# System_Wake_Interupt_Logic.net
KiCad netlist of a schematic drawn in Altium Designer
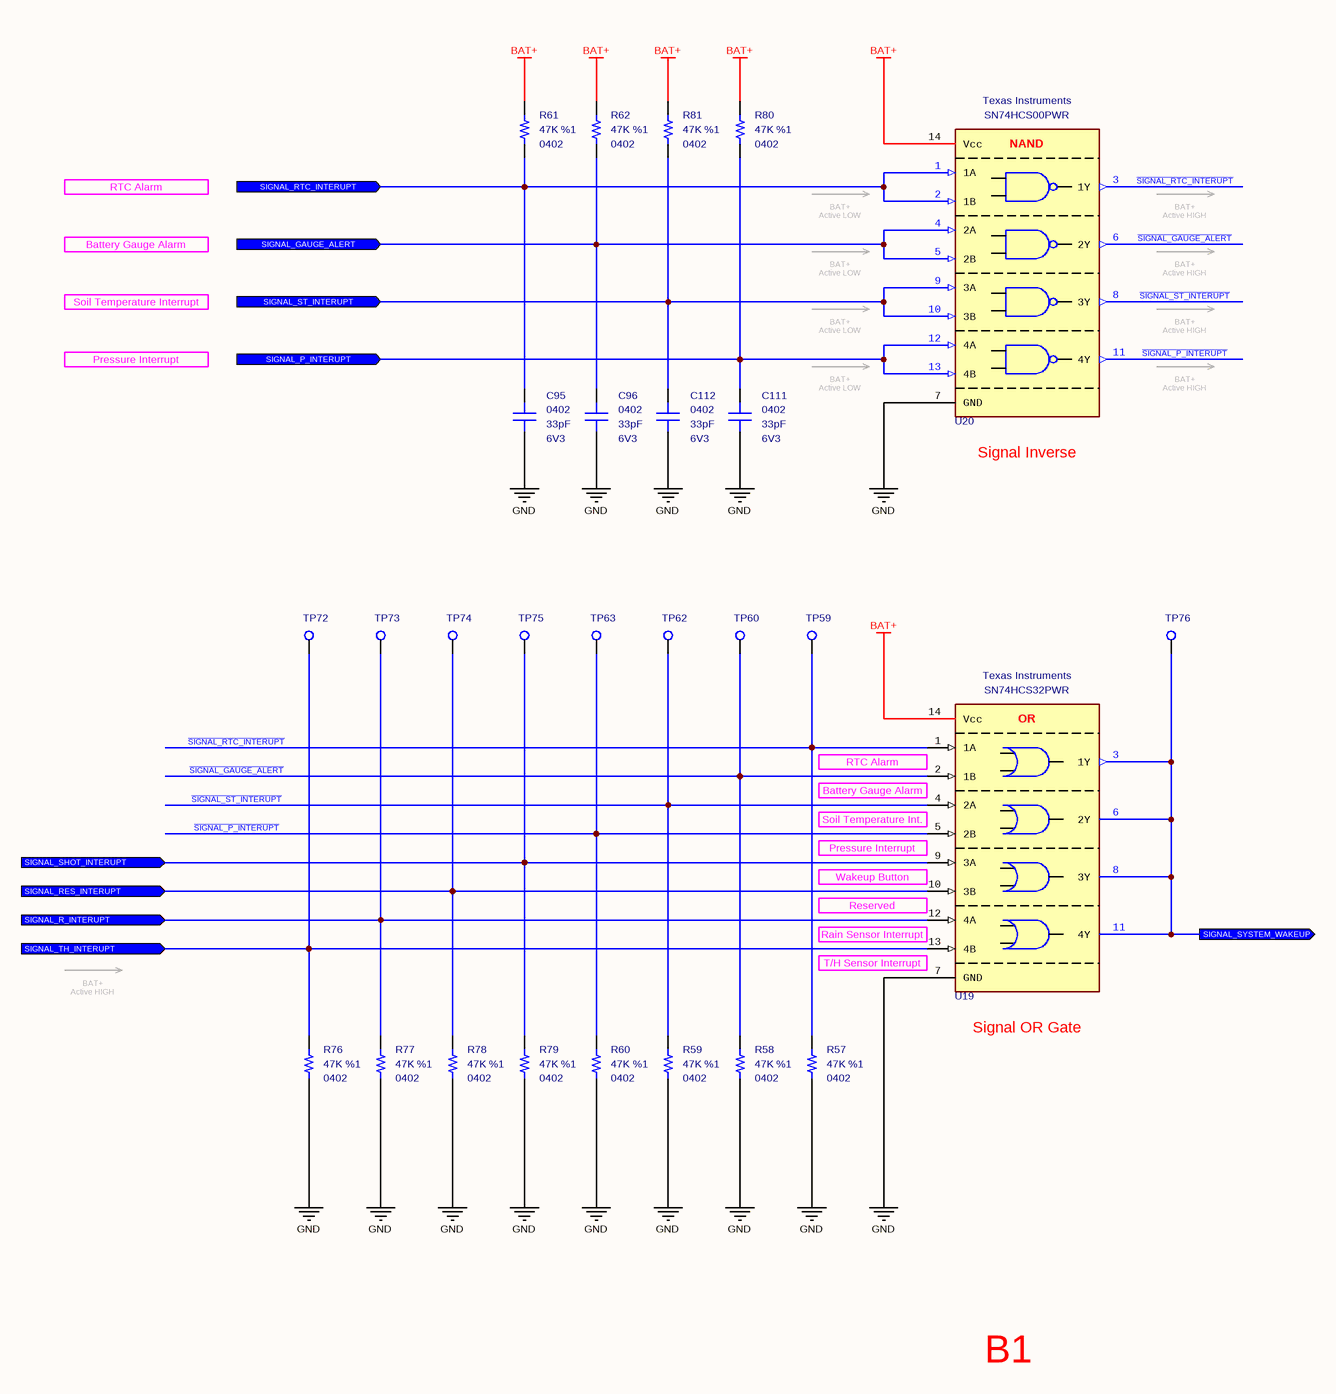
[diagram p0: System Wake Interupt Logic.SchDoc]

(export (version "E")
  (design (tool "Eeschema 10.0.6"))
  (components
    (comp (ref "C95")
      (value "33pF")
      (footprint "CAPACITOR_0402")
      (description "Capacitor - 33pF [0402] (Ceramic)")
      (fields
        (field (name "MANUFACTURER_PART_NUMBER") "C0402C330J9RACAUTO")
        (field (name "MOUSER_PART_NUMBER") "80-C0402C330J9RAUTO")
        (field (name "CASE") "0402")
        (field (name "VOLTAGE") "6V3")
      )
      (libsource (lib "Ovoo_Schematic") (part "Capacitor - 33pF [0402-6V3]"))
    )
    (comp (ref "C96")
      (value "33pF")
      (footprint "CAPACITOR_0402")
      (description "Capacitor - 33pF [0402] (Ceramic)")
      (fields
        (field (name "MANUFACTURER_PART_NUMBER") "C0402C330J9RACAUTO")
        (field (name "MOUSER_PART_NUMBER") "80-C0402C330J9RAUTO")
        (field (name "CASE") "0402")
        (field (name "VOLTAGE") "6V3")
      )
      (libsource (lib "Ovoo_Schematic") (part "Capacitor - 33pF [0402-6V3]"))
    )
    (comp (ref "C111")
      (value "33pF")
      (footprint "CAPACITOR_0402")
      (description "Capacitor - 33pF [0402] (Ceramic)")
      (fields
        (field (name "MANUFACTURER_PART_NUMBER") "C0402C330J9RACAUTO")
        (field (name "MOUSER_PART_NUMBER") "80-C0402C330J9RAUTO")
        (field (name "CASE") "0402")
        (field (name "VOLTAGE") "6V3")
      )
      (libsource (lib "Ovoo_Schematic") (part "Capacitor - 33pF [0402-6V3]"))
    )
    (comp (ref "C112")
      (value "33pF")
      (footprint "CAPACITOR_0402")
      (description "Capacitor - 33pF [0402] (Ceramic)")
      (fields
        (field (name "MANUFACTURER_PART_NUMBER") "C0402C330J9RACAUTO")
        (field (name "MOUSER_PART_NUMBER") "80-C0402C330J9RAUTO")
        (field (name "CASE") "0402")
        (field (name "VOLTAGE") "6V3")
      )
      (libsource (lib "Ovoo_Schematic") (part "Capacitor - 33pF [0402-6V3]"))
    )
    (comp (ref "R57")
      (value "47K")
      (footprint "RESISTOR_0402")
      (description "Thick Film Resistors - SMD 1/16 W 47 Kohms 1%")
      (fields
        (field (name "MANUFACTURER_PART_NUMBER") "CRCW040247K0FKED")
        (field (name "MOUSER_PART_NUMBER") "71-CRCW0402-47K-E3")
        (field (name "TOLERANCE") "%1")
        (field (name "CASE") "0402")
      )
      (libsource (lib "Ovoo_Schematic") (part "Resistor - 47K"))
    )
    (comp (ref "R58")
      (value "47K")
      (footprint "RESISTOR_0402")
      (description "Thick Film Resistors - SMD 1/16 W 47 Kohms 1%")
      (fields
        (field (name "MANUFACTURER_PART_NUMBER") "CRCW040247K0FKED")
        (field (name "MOUSER_PART_NUMBER") "71-CRCW0402-47K-E3")
        (field (name "TOLERANCE") "%1")
        (field (name "CASE") "0402")
      )
      (libsource (lib "Ovoo_Schematic") (part "Resistor - 47K"))
    )
    (comp (ref "R59")
      (value "47K")
      (footprint "RESISTOR_0402")
      (description "Thick Film Resistors - SMD 1/16 W 47 Kohms 1%")
      (fields
        (field (name "MANUFACTURER_PART_NUMBER") "CRCW040247K0FKED")
        (field (name "MOUSER_PART_NUMBER") "71-CRCW0402-47K-E3")
        (field (name "TOLERANCE") "%1")
        (field (name "CASE") "0402")
      )
      (libsource (lib "Ovoo_Schematic") (part "Resistor - 47K"))
    )
    (comp (ref "R60")
      (value "47K")
      (footprint "RESISTOR_0402")
      (description "Thick Film Resistors - SMD 1/16 W 47 Kohms 1%")
      (fields
        (field (name "MANUFACTURER_PART_NUMBER") "CRCW040247K0FKED")
        (field (name "MOUSER_PART_NUMBER") "71-CRCW0402-47K-E3")
        (field (name "TOLERANCE") "%1")
        (field (name "CASE") "0402")
      )
      (libsource (lib "Ovoo_Schematic") (part "Resistor - 47K"))
    )
    (comp (ref "R61")
      (value "47K")
      (footprint "RESISTOR_0402")
      (description "Thick Film Resistors - SMD 1/16 W 47 Kohms 1%")
      (fields
        (field (name "MANUFACTURER_PART_NUMBER") "CRCW040247K0FKED")
        (field (name "MOUSER_PART_NUMBER") "71-CRCW0402-47K-E3")
        (field (name "TOLERANCE") "%1")
        (field (name "CASE") "0402")
      )
      (libsource (lib "Ovoo_Schematic") (part "Resistor - 47K"))
    )
    (comp (ref "R62")
      (value "47K")
      (footprint "RESISTOR_0402")
      (description "Thick Film Resistors - SMD 1/16 W 47 Kohms 1%")
      (fields
        (field (name "MANUFACTURER_PART_NUMBER") "CRCW040247K0FKED")
        (field (name "MOUSER_PART_NUMBER") "71-CRCW0402-47K-E3")
        (field (name "TOLERANCE") "%1")
        (field (name "CASE") "0402")
      )
      (libsource (lib "Ovoo_Schematic") (part "Resistor - 47K"))
    )
    (comp (ref "R76")
      (value "47K")
      (footprint "RESISTOR_0402")
      (description "Thick Film Resistors - SMD 1/16 W 47 Kohms 1%")
      (fields
        (field (name "MANUFACTURER_PART_NUMBER") "CRCW040247K0FKED")
        (field (name "MOUSER_PART_NUMBER") "71-CRCW0402-47K-E3")
        (field (name "TOLERANCE") "%1")
        (field (name "CASE") "0402")
      )
      (libsource (lib "Ovoo_Schematic") (part "Resistor - 47K"))
    )
    (comp (ref "R77")
      (value "47K")
      (footprint "RESISTOR_0402")
      (description "Thick Film Resistors - SMD 1/16 W 47 Kohms 1%")
      (fields
        (field (name "MANUFACTURER_PART_NUMBER") "CRCW040247K0FKED")
        (field (name "MOUSER_PART_NUMBER") "71-CRCW0402-47K-E3")
        (field (name "TOLERANCE") "%1")
        (field (name "CASE") "0402")
      )
      (libsource (lib "Ovoo_Schematic") (part "Resistor - 47K"))
    )
    (comp (ref "R78")
      (value "47K")
      (footprint "RESISTOR_0402")
      (description "Thick Film Resistors - SMD 1/16 W 47 Kohms 1%")
      (fields
        (field (name "MANUFACTURER_PART_NUMBER") "CRCW040247K0FKED")
        (field (name "MOUSER_PART_NUMBER") "71-CRCW0402-47K-E3")
        (field (name "TOLERANCE") "%1")
        (field (name "CASE") "0402")
      )
      (libsource (lib "Ovoo_Schematic") (part "Resistor - 47K"))
    )
    (comp (ref "R79")
      (value "47K")
      (footprint "RESISTOR_0402")
      (description "Thick Film Resistors - SMD 1/16 W 47 Kohms 1%")
      (fields
        (field (name "MANUFACTURER_PART_NUMBER") "CRCW040247K0FKED")
        (field (name "MOUSER_PART_NUMBER") "71-CRCW0402-47K-E3")
        (field (name "TOLERANCE") "%1")
        (field (name "CASE") "0402")
      )
      (libsource (lib "Ovoo_Schematic") (part "Resistor - 47K"))
    )
    (comp (ref "R80")
      (value "47K")
      (footprint "RESISTOR_0402")
      (description "Thick Film Resistors - SMD 1/16 W 47 Kohms 1%")
      (fields
        (field (name "MANUFACTURER_PART_NUMBER") "CRCW040247K0FKED")
        (field (name "MOUSER_PART_NUMBER") "71-CRCW0402-47K-E3")
        (field (name "TOLERANCE") "%1")
        (field (name "CASE") "0402")
      )
      (libsource (lib "Ovoo_Schematic") (part "Resistor - 47K"))
    )
    (comp (ref "R81")
      (value "47K")
      (footprint "RESISTOR_0402")
      (description "Thick Film Resistors - SMD 1/16 W 47 Kohms 1%")
      (fields
        (field (name "MANUFACTURER_PART_NUMBER") "CRCW040247K0FKED")
        (field (name "MOUSER_PART_NUMBER") "71-CRCW0402-47K-E3")
        (field (name "TOLERANCE") "%1")
        (field (name "CASE") "0402")
      )
      (libsource (lib "Ovoo_Schematic") (part "Resistor - 47K"))
    )
    (comp (ref "TP59")
      (value "PCB - Test Point")
      (footprint "Test_Pad - Hole")
      (description "Test Point")
      (libsource (lib "Ovoo_Schematic") (part "PCB - Test Point"))
    )
    (comp (ref "TP60")
      (value "PCB - Test Point")
      (footprint "Test_Pad - Hole")
      (description "Test Point")
      (libsource (lib "Ovoo_Schematic") (part "PCB - Test Point"))
    )
    (comp (ref "TP62")
      (value "PCB - Test Point")
      (footprint "Test_Pad - Hole")
      (description "Test Point")
      (libsource (lib "Ovoo_Schematic") (part "PCB - Test Point"))
    )
    (comp (ref "TP63")
      (value "PCB - Test Point")
      (footprint "Test_Pad - Hole")
      (description "Test Point")
      (libsource (lib "Ovoo_Schematic") (part "PCB - Test Point"))
    )
    (comp (ref "TP72")
      (value "PCB - Test Point")
      (footprint "Test_Pad - Hole")
      (description "Test Point")
      (libsource (lib "Ovoo_Schematic") (part "PCB - Test Point"))
    )
    (comp (ref "TP73")
      (value "PCB - Test Point")
      (footprint "Test_Pad - Hole")
      (description "Test Point")
      (libsource (lib "Ovoo_Schematic") (part "PCB - Test Point"))
    )
    (comp (ref "TP74")
      (value "PCB - Test Point")
      (footprint "Test_Pad - Hole")
      (description "Test Point")
      (libsource (lib "Ovoo_Schematic") (part "PCB - Test Point"))
    )
    (comp (ref "TP75")
      (value "PCB - Test Point")
      (footprint "Test_Pad - Hole")
      (description "Test Point")
      (libsource (lib "Ovoo_Schematic") (part "PCB - Test Point"))
    )
    (comp (ref "TP76")
      (value "PCB - Test Point")
      (footprint "Test_Pad - Hole")
      (description "Test Point")
      (libsource (lib "Ovoo_Schematic") (part "PCB - Test Point"))
    )
    (comp (ref "U19")
      (value "Logic Gate (OR)")
      (footprint "TSSOP-14")
      (description "Logic Gates Quadruple 2-input OR gates with Schmitt-trigger inputs 14-TSSOP -40 to 125")
      (fields
        (field (name "MOUSER_PART_NUMBER") "595-SN74HCS32PWR")
        (field (name "MANUFACTURER_PART_NUMBER") "SN74HCS32PWR")
        (field (name "MANUFACTURER_NAME") "Texas Instruments")
      )
      (libsource (lib "Ovoo_Schematic") (part "IC - SN74HCS32"))
    )
    (comp (ref "U20")
      (value "Logic Gate (NAND)")
      (footprint "TSSOP-14")
      (description "Logic Gates Quadruple 2-input NAND gates with Schmitt-trigger inputs 14-TSSOP -40 to 125")
      (fields
        (field (name "MOUSER_PART_NUMBER") "595-SN74HCS00PWR")
        (field (name "MANUFACTURER_PART_NUMBER") "SN74HCS00PWR")
        (field (name "MANUFACTURER_NAME") "Texas Instruments")
      )
      (libsource (lib "Ovoo_Schematic") (part "IC - SN74HCS00"))
    )
  )
  (nets
    (net (code "1") (name "/SIGNAL_GAUGE_ALERT") (class "Default")
      (node (ref "C96") (pin "2") (pinfunction "2_2") (pintype "passive"))
      (node (ref "R62") (pin "1") (pinfunction "1_1") (pintype "passive"))
      (node (ref "U20") (pin "4") (pinfunction "2A_4") (pintype "input"))
      (node (ref "U20") (pin "5") (pinfunction "2B_5") (pintype "input"))
    )
    (net (code "2") (name "/SIGNAL_P_INTERUPT") (class "Default")
      (node (ref "C111") (pin "2") (pinfunction "2_2") (pintype "passive"))
      (node (ref "R80") (pin "1") (pinfunction "1_1") (pintype "passive"))
      (node (ref "U20") (pin "12") (pinfunction "4A_12") (pintype "input"))
      (node (ref "U20") (pin "13") (pinfunction "4B_13") (pintype "input"))
    )
    (net (code "3") (name "/SIGNAL_RES_INTERUPT") (class "Default")
      (node (ref "R78") (pin "2") (pinfunction "2_2") (pintype "passive"))
      (node (ref "TP74") (pin "1") (pinfunction "1_1") (pintype "passive"))
      (node (ref "U19") (pin "10") (pinfunction "3B_10") (pintype "input"))
    )
    (net (code "4") (name "/SIGNAL_RTC_INTERUPT") (class "Default")
      (node (ref "C95") (pin "2") (pinfunction "2_2") (pintype "passive"))
      (node (ref "R61") (pin "1") (pinfunction "1_1") (pintype "passive"))
      (node (ref "U20") (pin "1") (pinfunction "1A_1") (pintype "input"))
      (node (ref "U20") (pin "2") (pinfunction "1B_2") (pintype "input"))
    )
    (net (code "5") (name "/SIGNAL_R_INTERUPT") (class "Default")
      (node (ref "R77") (pin "2") (pinfunction "2_2") (pintype "passive"))
      (node (ref "TP73") (pin "1") (pinfunction "1_1") (pintype "passive"))
      (node (ref "U19") (pin "12") (pinfunction "4A_12") (pintype "input"))
    )
    (net (code "6") (name "/SIGNAL_SHOT_INTERUPT") (class "Default")
      (node (ref "R79") (pin "2") (pinfunction "2_2") (pintype "passive"))
      (node (ref "TP75") (pin "1") (pinfunction "1_1") (pintype "passive"))
      (node (ref "U19") (pin "9") (pinfunction "3A_9") (pintype "input"))
    )
    (net (code "7") (name "/SIGNAL_ST_INTERUPT") (class "Default")
      (node (ref "C112") (pin "2") (pinfunction "2_2") (pintype "passive"))
      (node (ref "R81") (pin "1") (pinfunction "1_1") (pintype "passive"))
      (node (ref "U20") (pin "10") (pinfunction "3B_10") (pintype "input"))
      (node (ref "U20") (pin "9") (pinfunction "3A_9") (pintype "input"))
    )
    (net (code "8") (name "/SIGNAL_SYSTEM_WAKEUP") (class "Default")
      (node (ref "TP76") (pin "1") (pinfunction "1_1") (pintype "passive"))
      (node (ref "U19") (pin "11") (pinfunction "4Y_11") (pintype "passive"))
      (node (ref "U19") (pin "3") (pinfunction "1Y_3") (pintype "output"))
      (node (ref "U19") (pin "6") (pinfunction "2Y_6") (pintype "passive"))
      (node (ref "U19") (pin "8") (pinfunction "3Y_8") (pintype "passive"))
    )
    (net (code "9") (name "/SIGNAL_TH_INTERUPT") (class "Default")
      (node (ref "R76") (pin "2") (pinfunction "2_2") (pintype "passive"))
      (node (ref "TP72") (pin "1") (pinfunction "1_1") (pintype "passive"))
      (node (ref "U19") (pin "13") (pinfunction "4B_13") (pintype "input"))
    )
    (net (code "10") (name "/~{SIGNAL_GAUGE_ALERT}") (class "Default")
      (node (ref "R58") (pin "2") (pinfunction "2_2") (pintype "passive"))
      (node (ref "TP60") (pin "1") (pinfunction "1_1") (pintype "passive"))
      (node (ref "U19") (pin "2") (pinfunction "1B_2") (pintype "input"))
      (node (ref "U20") (pin "6") (pinfunction "2Y_6") (pintype "output"))
    )
    (net (code "11") (name "/~{SIGNAL_P_INTERUPT}") (class "Default")
      (node (ref "R60") (pin "2") (pinfunction "2_2") (pintype "passive"))
      (node (ref "TP63") (pin "1") (pinfunction "1_1") (pintype "passive"))
      (node (ref "U19") (pin "5") (pinfunction "2B_5") (pintype "input"))
      (node (ref "U20") (pin "11") (pinfunction "4Y_11") (pintype "output"))
    )
    (net (code "12") (name "/~{SIGNAL_RTC_INTERUPT}") (class "Default")
      (node (ref "R57") (pin "2") (pinfunction "2_2") (pintype "passive"))
      (node (ref "TP59") (pin "1") (pinfunction "1_1") (pintype "passive"))
      (node (ref "U19") (pin "1") (pinfunction "1A_1") (pintype "input"))
      (node (ref "U20") (pin "3") (pinfunction "1Y_3") (pintype "output"))
    )
    (net (code "13") (name "/~{SIGNAL_ST_INTERUPT}") (class "Default")
      (node (ref "R59") (pin "2") (pinfunction "2_2") (pintype "passive"))
      (node (ref "TP62") (pin "1") (pinfunction "1_1") (pintype "passive"))
      (node (ref "U19") (pin "4") (pinfunction "2A_4") (pintype "input"))
      (node (ref "U20") (pin "8") (pinfunction "3Y_8") (pintype "output"))
    )
    (net (code "14") (name "BAT+") (class "Default")
      (node (ref "R61") (pin "2") (pinfunction "2_2") (pintype "passive"))
      (node (ref "R62") (pin "2") (pinfunction "2_2") (pintype "passive"))
      (node (ref "R80") (pin "2") (pinfunction "2_2") (pintype "passive"))
      (node (ref "R81") (pin "2") (pinfunction "2_2") (pintype "passive"))
      (node (ref "U19") (pin "14") (pinfunction "Vcc_14") (pintype "power_in"))
      (node (ref "U20") (pin "14") (pinfunction "Vcc_14") (pintype "power_in"))
    )
    (net (code "15") (name "GND") (class "Default")
      (node (ref "C111") (pin "1") (pinfunction "1_1") (pintype "passive"))
      (node (ref "C112") (pin "1") (pinfunction "1_1") (pintype "passive"))
      (node (ref "C95") (pin "1") (pinfunction "1_1") (pintype "passive"))
      (node (ref "C96") (pin "1") (pinfunction "1_1") (pintype "passive"))
      (node (ref "R57") (pin "1") (pinfunction "1_1") (pintype "passive"))
      (node (ref "R58") (pin "1") (pinfunction "1_1") (pintype "passive"))
      (node (ref "R59") (pin "1") (pinfunction "1_1") (pintype "passive"))
      (node (ref "R60") (pin "1") (pinfunction "1_1") (pintype "passive"))
      (node (ref "R76") (pin "1") (pinfunction "1_1") (pintype "passive"))
      (node (ref "R77") (pin "1") (pinfunction "1_1") (pintype "passive"))
      (node (ref "R78") (pin "1") (pinfunction "1_1") (pintype "passive"))
      (node (ref "R79") (pin "1") (pinfunction "1_1") (pintype "passive"))
      (node (ref "U19") (pin "7") (pinfunction "GND_7") (pintype "power_in"))
      (node (ref "U20") (pin "7") (pinfunction "GND_7") (pintype "power_in"))
    )
  )
)
